# Relay_circuit_12V.net
KiCad netlist of a schematic drawn in Altium Designer
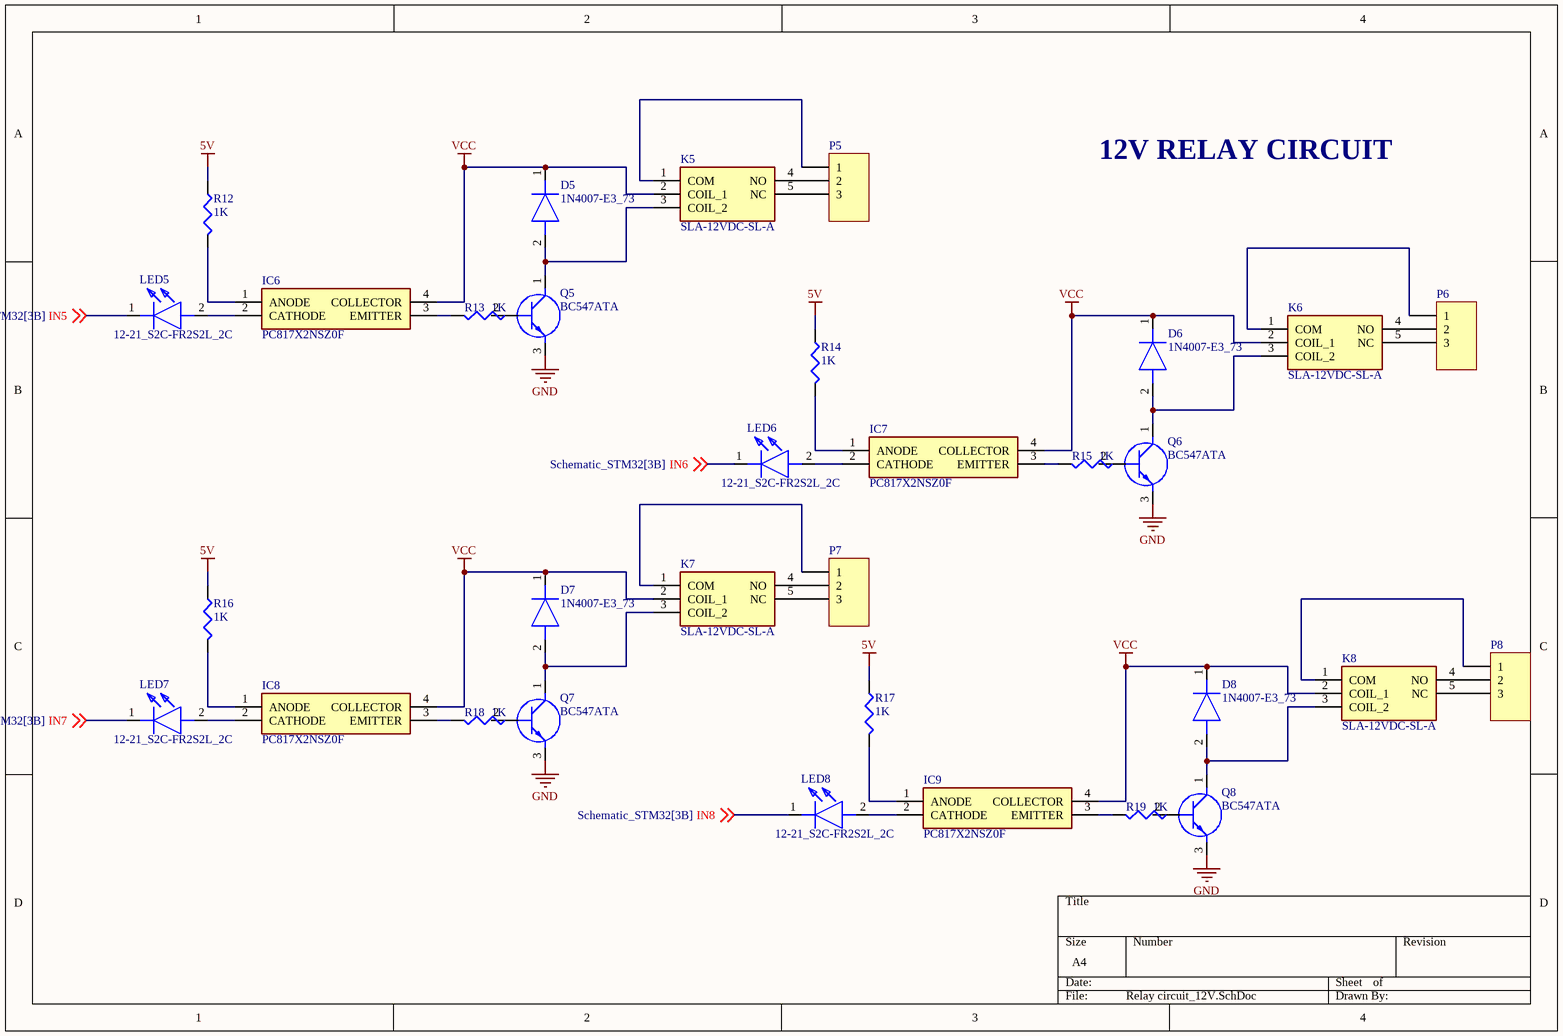
[diagram p0: Relay circuit_12V.SchDoc]

(export (version "E")
  (design (tool "Eeschema 10.0.6"))
  (components
    (comp (ref "D5")
      (value "1N4007-E3_73")
      (footprint "SamacSys:DIOAD1405W86L465D235")
      (description "Diode")
      (fields
        (field (name "MANUFACTURER_PART_NUMBER") "1N4007-E3/73")
        (field (name "MOUSER PART NUMBER") "625-1N4007-E3/73")
      )
      (libsource (lib "*") (part "1N4007-E3_73"))
    )
    (comp (ref "D6")
      (value "1N4007-E3_73")
      (footprint "SamacSys:DIOAD1405W86L465D235")
      (description "Diode")
      (fields
        (field (name "MANUFACTURER_PART_NUMBER") "1N4007-E3/73")
        (field (name "MOUSER PART NUMBER") "625-1N4007-E3/73")
      )
      (libsource (lib "*") (part "1N4007-E3_73"))
    )
    (comp (ref "D7")
      (value "1N4007-E3_73")
      (footprint "SamacSys:DIOAD1405W86L465D235")
      (description "Diode")
      (fields
        (field (name "MANUFACTURER_PART_NUMBER") "1N4007-E3/73")
        (field (name "MOUSER PART NUMBER") "625-1N4007-E3/73")
      )
      (libsource (lib "*") (part "1N4007-E3_73"))
    )
    (comp (ref "D8")
      (value "1N4007-E3_73")
      (footprint "SamacSys:DIOAD1405W86L465D235")
      (description "Diode")
      (fields
        (field (name "MANUFACTURER_PART_NUMBER") "1N4007-E3/73")
        (field (name "MOUSER PART NUMBER") "625-1N4007-E3/73")
      )
      (libsource (lib "*") (part "1N4007-E3_73"))
    )
    (comp (ref "IC6")
      (value "PC817X2NSZ0F")
      (footprint "SamacSys:DIP762W60P254L458H400Q4N")
      (description "Integrated Circuit")
      (libsource (lib "*") (part "PC817X2NSZ0F"))
    )
    (comp (ref "IC7")
      (value "PC817X2NSZ0F")
      (footprint "SamacSys:DIP762W60P254L458H400Q4N")
      (description "Integrated Circuit")
      (libsource (lib "*") (part "PC817X2NSZ0F"))
    )
    (comp (ref "IC8")
      (value "PC817X2NSZ0F")
      (footprint "SamacSys:DIP762W60P254L458H400Q4N")
      (description "Integrated Circuit")
      (libsource (lib "*") (part "PC817X2NSZ0F"))
    )
    (comp (ref "IC9")
      (value "PC817X2NSZ0F")
      (footprint "SamacSys:DIP762W60P254L458H400Q4N")
      (description "Integrated Circuit")
      (libsource (lib "*") (part "PC817X2NSZ0F"))
    )
    (comp (ref "K5")
      (value "SLA-12VDC-SL-A")
      (footprint "SamacSys:SLA12VDCSLA")
      (description "Relay or Contactor")
      (libsource (lib "*") (part "SLA-12VDC-SL-A"))
    )
    (comp (ref "K6")
      (value "SLA-12VDC-SL-A")
      (footprint "SamacSys:SLA12VDCSLA")
      (description "Relay or Contactor")
      (libsource (lib "*") (part "SLA-12VDC-SL-A"))
    )
    (comp (ref "K7")
      (value "SLA-12VDC-SL-A")
      (footprint "SamacSys:SLA12VDCSLA")
      (description "Relay or Contactor")
      (libsource (lib "*") (part "SLA-12VDC-SL-A"))
    )
    (comp (ref "K8")
      (value "SLA-12VDC-SL-A")
      (footprint "SamacSys:SLA12VDCSLA")
      (description "Relay or Contactor")
      (libsource (lib "*") (part "SLA-12VDC-SL-A"))
    )
    (comp (ref "LED5")
      (value "12-21_S2C-FR2S2L_2C")
      (footprint "SamacSys:1221S2CFR2S2L2C")
      (description "LED")
      (fields (field (name "MANUFACTURER_PART_NUMBER") "12-21/S2C-FR2S2L/2C"))
      (libsource (lib "*") (part "12-21_S2C-FR2S2L_2C"))
    )
    (comp (ref "LED6")
      (value "12-21_S2C-FR2S2L_2C")
      (footprint "SamacSys:1221S2CFR2S2L2C")
      (description "LED")
      (fields (field (name "MANUFACTURER_PART_NUMBER") "12-21/S2C-FR2S2L/2C"))
      (libsource (lib "*") (part "12-21_S2C-FR2S2L_2C"))
    )
    (comp (ref "LED7")
      (value "12-21_S2C-FR2S2L_2C")
      (footprint "SamacSys:1221S2CFR2S2L2C")
      (description "LED")
      (fields (field (name "MANUFACTURER_PART_NUMBER") "12-21/S2C-FR2S2L/2C"))
      (libsource (lib "*") (part "12-21_S2C-FR2S2L_2C"))
    )
    (comp (ref "LED8")
      (value "12-21_S2C-FR2S2L_2C")
      (footprint "SamacSys:1221S2CFR2S2L2C")
      (description "LED")
      (fields (field (name "MANUFACTURER_PART_NUMBER") "12-21/S2C-FR2S2L/2C"))
      (libsource (lib "*") (part "12-21_S2C-FR2S2L_2C"))
    )
    (comp (ref "P5")
      (value "Header 3")
      (footprint "CON4PIN5MM")
      (description "Header, 4-Pin")
      (fields (field (name "PUBLISHER") "Altium Limited"))
      (libsource (lib "Miscellaneous Connectors") (part "Header 4"))
    )
    (comp (ref "P6")
      (value "Header 3")
      (footprint "CON4PIN5MM")
      (description "Header, 4-Pin")
      (fields (field (name "PUBLISHER") "Altium Limited"))
      (libsource (lib "Miscellaneous Connectors") (part "Header 4"))
    )
    (comp (ref "P7")
      (value "Header 3")
      (footprint "CON4PIN5MM")
      (description "Header, 4-Pin")
      (fields (field (name "PUBLISHER") "Altium Limited"))
      (libsource (lib "Miscellaneous Connectors") (part "Header 4"))
    )
    (comp (ref "P8")
      (value "Header 3")
      (footprint "CON4PIN5MM")
      (description "Header, 4-Pin")
      (fields (field (name "PUBLISHER") "Altium Limited"))
      (libsource (lib "Miscellaneous Connectors") (part "Header 4"))
    )
    (comp (ref "Q5")
      (value "BC547ATA")
      (footprint "SamacSys:TO-92_(TO-226)")
      (description "Transistor BJT NPN")
      (fields (field (name "MOUSER PART NUMBER") "512-BC547ATA"))
      (libsource (lib "*") (part "BC547ATA"))
    )
    (comp (ref "Q6")
      (value "BC547ATA")
      (footprint "SamacSys:TO-92_(TO-226)")
      (description "Transistor BJT NPN")
      (fields (field (name "MOUSER PART NUMBER") "512-BC547ATA"))
      (libsource (lib "*") (part "BC547ATA"))
    )
    (comp (ref "Q7")
      (value "BC547ATA")
      (footprint "SamacSys:TO-92_(TO-226)")
      (description "Transistor BJT NPN")
      (fields (field (name "MOUSER PART NUMBER") "512-BC547ATA"))
      (libsource (lib "*") (part "BC547ATA"))
    )
    (comp (ref "Q8")
      (value "BC547ATA")
      (footprint "SamacSys:TO-92_(TO-226)")
      (description "Transistor BJT NPN")
      (fields (field (name "MOUSER PART NUMBER") "512-BC547ATA"))
      (libsource (lib "*") (part "BC547ATA"))
    )
    (comp (ref "R12")
      (value "1K")
      (footprint "J1-0603")
      (description "Resistor")
      (fields (field (name "Comment") "Res3") (field (name "PUBLISHER") "Altium Limited"))
      (libsource (lib "Miscellaneous Devices") (part "Res3"))
    )
    (comp (ref "R13")
      (value "1K")
      (footprint "J1-0603")
      (description "Resistor")
      (fields (field (name "Comment") "Res3") (field (name "PUBLISHER") "Altium Limited"))
      (libsource (lib "Miscellaneous Devices") (part "Res3"))
    )
    (comp (ref "R14")
      (value "1K")
      (footprint "J1-0603")
      (description "Resistor")
      (fields (field (name "Comment") "Res3") (field (name "PUBLISHER") "Altium Limited"))
      (libsource (lib "Miscellaneous Devices") (part "Res3"))
    )
    (comp (ref "R15")
      (value "1K")
      (footprint "J1-0603")
      (description "Resistor")
      (fields (field (name "Comment") "Res3") (field (name "PUBLISHER") "Altium Limited"))
      (libsource (lib "Miscellaneous Devices") (part "Res3"))
    )
    (comp (ref "R16")
      (value "1K")
      (footprint "J1-0603")
      (description "Resistor")
      (fields (field (name "Comment") "Res3") (field (name "PUBLISHER") "Altium Limited"))
      (libsource (lib "Miscellaneous Devices") (part "Res3"))
    )
    (comp (ref "R17")
      (value "1K")
      (footprint "J1-0603")
      (description "Resistor")
      (fields (field (name "Comment") "Res3") (field (name "PUBLISHER") "Altium Limited"))
      (libsource (lib "Miscellaneous Devices") (part "Res3"))
    )
    (comp (ref "R18")
      (value "1K")
      (footprint "J1-0603")
      (description "Resistor")
      (fields (field (name "Comment") "Res3") (field (name "PUBLISHER") "Altium Limited"))
      (libsource (lib "Miscellaneous Devices") (part "Res3"))
    )
    (comp (ref "R19")
      (value "1K")
      (footprint "J1-0603")
      (description "Resistor")
      (fields (field (name "Comment") "Res3") (field (name "PUBLISHER") "Altium Limited"))
      (libsource (lib "Miscellaneous Devices") (part "Res3"))
    )
  )
  (nets
    (net (code "1") (name "5V") (class "Default")
      (node (ref "R12") (pin "1") (pinfunction "1_1") (pintype "passive"))
      (node (ref "R14") (pin "1") (pinfunction "1_1") (pintype "passive"))
      (node (ref "R16") (pin "1") (pinfunction "1_1") (pintype "passive"))
      (node (ref "R17") (pin "1") (pinfunction "1_1") (pintype "passive"))
    )
    (net (code "2") (name "GND") (class "Default")
      (node (ref "Q5") (pin "3") (pinfunction "E_3") (pintype "passive"))
      (node (ref "Q6") (pin "3") (pinfunction "E_3") (pintype "passive"))
      (node (ref "Q7") (pin "3") (pinfunction "E_3") (pintype "passive"))
      (node (ref "Q8") (pin "3") (pinfunction "E_3") (pintype "passive"))
    )
    (net (code "3") (name "IN5") (class "Default")
      (node (ref "LED5") (pin "1") (pinfunction "K_1") (pintype "passive"))
    )
    (net (code "4") (name "IN6") (class "Default")
      (node (ref "LED6") (pin "1") (pinfunction "K_1") (pintype "passive"))
    )
    (net (code "5") (name "IN7") (class "Default")
      (node (ref "LED7") (pin "1") (pinfunction "K_1") (pintype "passive"))
    )
    (net (code "6") (name "IN8") (class "Default")
      (node (ref "LED8") (pin "1") (pinfunction "K_1") (pintype "passive"))
    )
    (net (code "7") (name "Net-(D5-A)") (class "Default")
      (node (ref "D5") (pin "2") (pinfunction "A_2") (pintype "passive"))
      (node (ref "K5") (pin "3") (pinfunction "COIL_2_3") (pintype "passive"))
      (node (ref "Q5") (pin "1") (pinfunction "C_1") (pintype "passive"))
    )
    (net (code "8") (name "Net-(D6-A)") (class "Default")
      (node (ref "D6") (pin "2") (pinfunction "A_2") (pintype "passive"))
      (node (ref "K6") (pin "3") (pinfunction "COIL_2_3") (pintype "passive"))
      (node (ref "Q6") (pin "1") (pinfunction "C_1") (pintype "passive"))
    )
    (net (code "9") (name "Net-(D7-A)") (class "Default")
      (node (ref "D7") (pin "2") (pinfunction "A_2") (pintype "passive"))
      (node (ref "K7") (pin "3") (pinfunction "COIL_2_3") (pintype "passive"))
      (node (ref "Q7") (pin "1") (pinfunction "C_1") (pintype "passive"))
    )
    (net (code "10") (name "Net-(D8-A)") (class "Default")
      (node (ref "D8") (pin "2") (pinfunction "A_2") (pintype "passive"))
      (node (ref "K8") (pin "3") (pinfunction "COIL_2_3") (pintype "passive"))
      (node (ref "Q8") (pin "1") (pinfunction "C_1") (pintype "passive"))
    )
    (net (code "11") (name "Net-(IC6-ANODE)") (class "Default")
      (node (ref "IC6") (pin "1") (pinfunction "ANODE_1") (pintype "passive"))
      (node (ref "R12") (pin "2") (pinfunction "2_2") (pintype "passive"))
    )
    (net (code "12") (name "Net-(IC6-CATHODE)") (class "Default")
      (node (ref "IC6") (pin "2") (pinfunction "CATHODE_2") (pintype "passive"))
      (node (ref "LED5") (pin "2") (pinfunction "A_2") (pintype "passive"))
    )
    (net (code "13") (name "Net-(IC6-EMITTER)") (class "Default")
      (node (ref "IC6") (pin "3") (pinfunction "EMITTER_3") (pintype "passive"))
      (node (ref "R13") (pin "2") (pinfunction "2_2") (pintype "passive"))
    )
    (net (code "14") (name "Net-(IC7-ANODE)") (class "Default")
      (node (ref "IC7") (pin "1") (pinfunction "ANODE_1") (pintype "passive"))
      (node (ref "R14") (pin "2") (pinfunction "2_2") (pintype "passive"))
    )
    (net (code "15") (name "Net-(IC7-CATHODE)") (class "Default")
      (node (ref "IC7") (pin "2") (pinfunction "CATHODE_2") (pintype "passive"))
      (node (ref "LED6") (pin "2") (pinfunction "A_2") (pintype "passive"))
    )
    (net (code "16") (name "Net-(IC7-EMITTER)") (class "Default")
      (node (ref "IC7") (pin "3") (pinfunction "EMITTER_3") (pintype "passive"))
      (node (ref "R15") (pin "2") (pinfunction "2_2") (pintype "passive"))
    )
    (net (code "17") (name "Net-(IC8-ANODE)") (class "Default")
      (node (ref "IC8") (pin "1") (pinfunction "ANODE_1") (pintype "passive"))
      (node (ref "R16") (pin "2") (pinfunction "2_2") (pintype "passive"))
    )
    (net (code "18") (name "Net-(IC8-CATHODE)") (class "Default")
      (node (ref "IC8") (pin "2") (pinfunction "CATHODE_2") (pintype "passive"))
      (node (ref "LED7") (pin "2") (pinfunction "A_2") (pintype "passive"))
    )
    (net (code "19") (name "Net-(IC8-EMITTER)") (class "Default")
      (node (ref "IC8") (pin "3") (pinfunction "EMITTER_3") (pintype "passive"))
      (node (ref "R18") (pin "2") (pinfunction "2_2") (pintype "passive"))
    )
    (net (code "20") (name "Net-(IC9-ANODE)") (class "Default")
      (node (ref "IC9") (pin "1") (pinfunction "ANODE_1") (pintype "passive"))
      (node (ref "R17") (pin "2") (pinfunction "2_2") (pintype "passive"))
    )
    (net (code "21") (name "Net-(IC9-CATHODE)") (class "Default")
      (node (ref "IC9") (pin "2") (pinfunction "CATHODE_2") (pintype "passive"))
      (node (ref "LED8") (pin "2") (pinfunction "A_2") (pintype "passive"))
    )
    (net (code "22") (name "Net-(IC9-EMITTER)") (class "Default")
      (node (ref "IC9") (pin "3") (pinfunction "EMITTER_3") (pintype "passive"))
      (node (ref "R19") (pin "2") (pinfunction "2_2") (pintype "passive"))
    )
    (net (code "23") (name "Net-(K5-COM)") (class "Default")
      (node (ref "K5") (pin "1") (pinfunction "COM_1") (pintype "passive"))
      (node (ref "P5") (pin "1") (pinfunction "1_1") (pintype "passive"))
    )
    (net (code "24") (name "Net-(K5-NC)") (class "Default")
      (node (ref "K5") (pin "5") (pinfunction "NC_5") (pintype "passive"))
      (node (ref "P5") (pin "3") (pinfunction "3_3") (pintype "passive"))
    )
    (net (code "25") (name "Net-(K5-NO)") (class "Default")
      (node (ref "K5") (pin "4") (pinfunction "NO_4") (pintype "passive"))
      (node (ref "P5") (pin "2") (pinfunction "2_2") (pintype "passive"))
    )
    (net (code "26") (name "Net-(K6-COM)") (class "Default")
      (node (ref "K6") (pin "1") (pinfunction "COM_1") (pintype "passive"))
      (node (ref "P6") (pin "1") (pinfunction "1_1") (pintype "passive"))
    )
    (net (code "27") (name "Net-(K6-NC)") (class "Default")
      (node (ref "K6") (pin "5") (pinfunction "NC_5") (pintype "passive"))
      (node (ref "P6") (pin "3") (pinfunction "3_3") (pintype "passive"))
    )
    (net (code "28") (name "Net-(K6-NO)") (class "Default")
      (node (ref "K6") (pin "4") (pinfunction "NO_4") (pintype "passive"))
      (node (ref "P6") (pin "2") (pinfunction "2_2") (pintype "passive"))
    )
    (net (code "29") (name "Net-(K7-COM)") (class "Default")
      (node (ref "K7") (pin "1") (pinfunction "COM_1") (pintype "passive"))
      (node (ref "P7") (pin "1") (pinfunction "1_1") (pintype "passive"))
    )
    (net (code "30") (name "Net-(K7-NC)") (class "Default")
      (node (ref "K7") (pin "5") (pinfunction "NC_5") (pintype "passive"))
      (node (ref "P7") (pin "3") (pinfunction "3_3") (pintype "passive"))
    )
    (net (code "31") (name "Net-(K7-NO)") (class "Default")
      (node (ref "K7") (pin "4") (pinfunction "NO_4") (pintype "passive"))
      (node (ref "P7") (pin "2") (pinfunction "2_2") (pintype "passive"))
    )
    (net (code "32") (name "Net-(K8-COM)") (class "Default")
      (node (ref "K8") (pin "1") (pinfunction "COM_1") (pintype "passive"))
      (node (ref "P8") (pin "1") (pinfunction "1_1") (pintype "passive"))
    )
    (net (code "33") (name "Net-(K8-NC)") (class "Default")
      (node (ref "K8") (pin "5") (pinfunction "NC_5") (pintype "passive"))
      (node (ref "P8") (pin "3") (pinfunction "3_3") (pintype "passive"))
    )
    (net (code "34") (name "Net-(K8-NO)") (class "Default")
      (node (ref "K8") (pin "4") (pinfunction "NO_4") (pintype "passive"))
      (node (ref "P8") (pin "2") (pinfunction "2_2") (pintype "passive"))
    )
    (net (code "35") (name "VCC") (class "Default")
      (node (ref "D5") (pin "1") (pinfunction "K_1") (pintype "passive"))
      (node (ref "D6") (pin "1") (pinfunction "K_1") (pintype "passive"))
      (node (ref "D7") (pin "1") (pinfunction "K_1") (pintype "passive"))
      (node (ref "D8") (pin "1") (pinfunction "K_1") (pintype "passive"))
      (node (ref "IC6") (pin "4") (pinfunction "COLLECTOR_4") (pintype "passive"))
      (node (ref "IC7") (pin "4") (pinfunction "COLLECTOR_4") (pintype "passive"))
      (node (ref "IC8") (pin "4") (pinfunction "COLLECTOR_4") (pintype "passive"))
      (node (ref "IC9") (pin "4") (pinfunction "COLLECTOR_4") (pintype "passive"))
      (node (ref "K5") (pin "2") (pinfunction "COIL_1_2") (pintype "passive"))
      (node (ref "K6") (pin "2") (pinfunction "COIL_1_2") (pintype "passive"))
      (node (ref "K7") (pin "2") (pinfunction "COIL_1_2") (pintype "passive"))
      (node (ref "K8") (pin "2") (pinfunction "COIL_1_2") (pintype "passive"))
    )
    (net (code "36") (name "unconnected-(P5-Pad4)") (class "Default")
      (node (ref "P5") (pin "4") (pinfunction "4_4") (pintype "passive"))
    )
    (net (code "37") (name "unconnected-(P6-Pad4)") (class "Default")
      (node (ref "P6") (pin "4") (pinfunction "4_4") (pintype "passive"))
    )
    (net (code "38") (name "unconnected-(P7-Pad4)") (class "Default")
      (node (ref "P7") (pin "4") (pinfunction "4_4") (pintype "passive"))
    )
    (net (code "39") (name "unconnected-(P8-Pad4)") (class "Default")
      (node (ref "P8") (pin "4") (pinfunction "4_4") (pintype "passive"))
    )
    (net (code "40") (name "unconnected-(Q5-B-Pad2)") (class "Default")
      (node (ref "Q5") (pin "2") (pinfunction "B_2") (pintype "passive"))
    )
    (net (code "41") (name "unconnected-(Q6-B-Pad2)") (class "Default")
      (node (ref "Q6") (pin "2") (pinfunction "B_2") (pintype "passive"))
    )
    (net (code "42") (name "unconnected-(Q7-B-Pad2)") (class "Default")
      (node (ref "Q7") (pin "2") (pinfunction "B_2") (pintype "passive"))
    )
    (net (code "43") (name "unconnected-(Q8-B-Pad2)") (class "Default")
      (node (ref "Q8") (pin "2") (pinfunction "B_2") (pintype "passive"))
    )
    (net (code "44") (name "unconnected-(R13-Pad1)") (class "Default")
      (node (ref "R13") (pin "1") (pinfunction "1_1") (pintype "passive"))
    )
    (net (code "45") (name "unconnected-(R15-Pad1)") (class "Default")
      (node (ref "R15") (pin "1") (pinfunction "1_1") (pintype "passive"))
    )
    (net (code "46") (name "unconnected-(R18-Pad1)") (class "Default")
      (node (ref "R18") (pin "1") (pinfunction "1_1") (pintype "passive"))
    )
    (net (code "47") (name "unconnected-(R19-Pad1)") (class "Default")
      (node (ref "R19") (pin "1") (pinfunction "1_1") (pintype "passive"))
    )
  )
)
